# MCU.net
KiCad netlist of a schematic drawn in Altium Designer
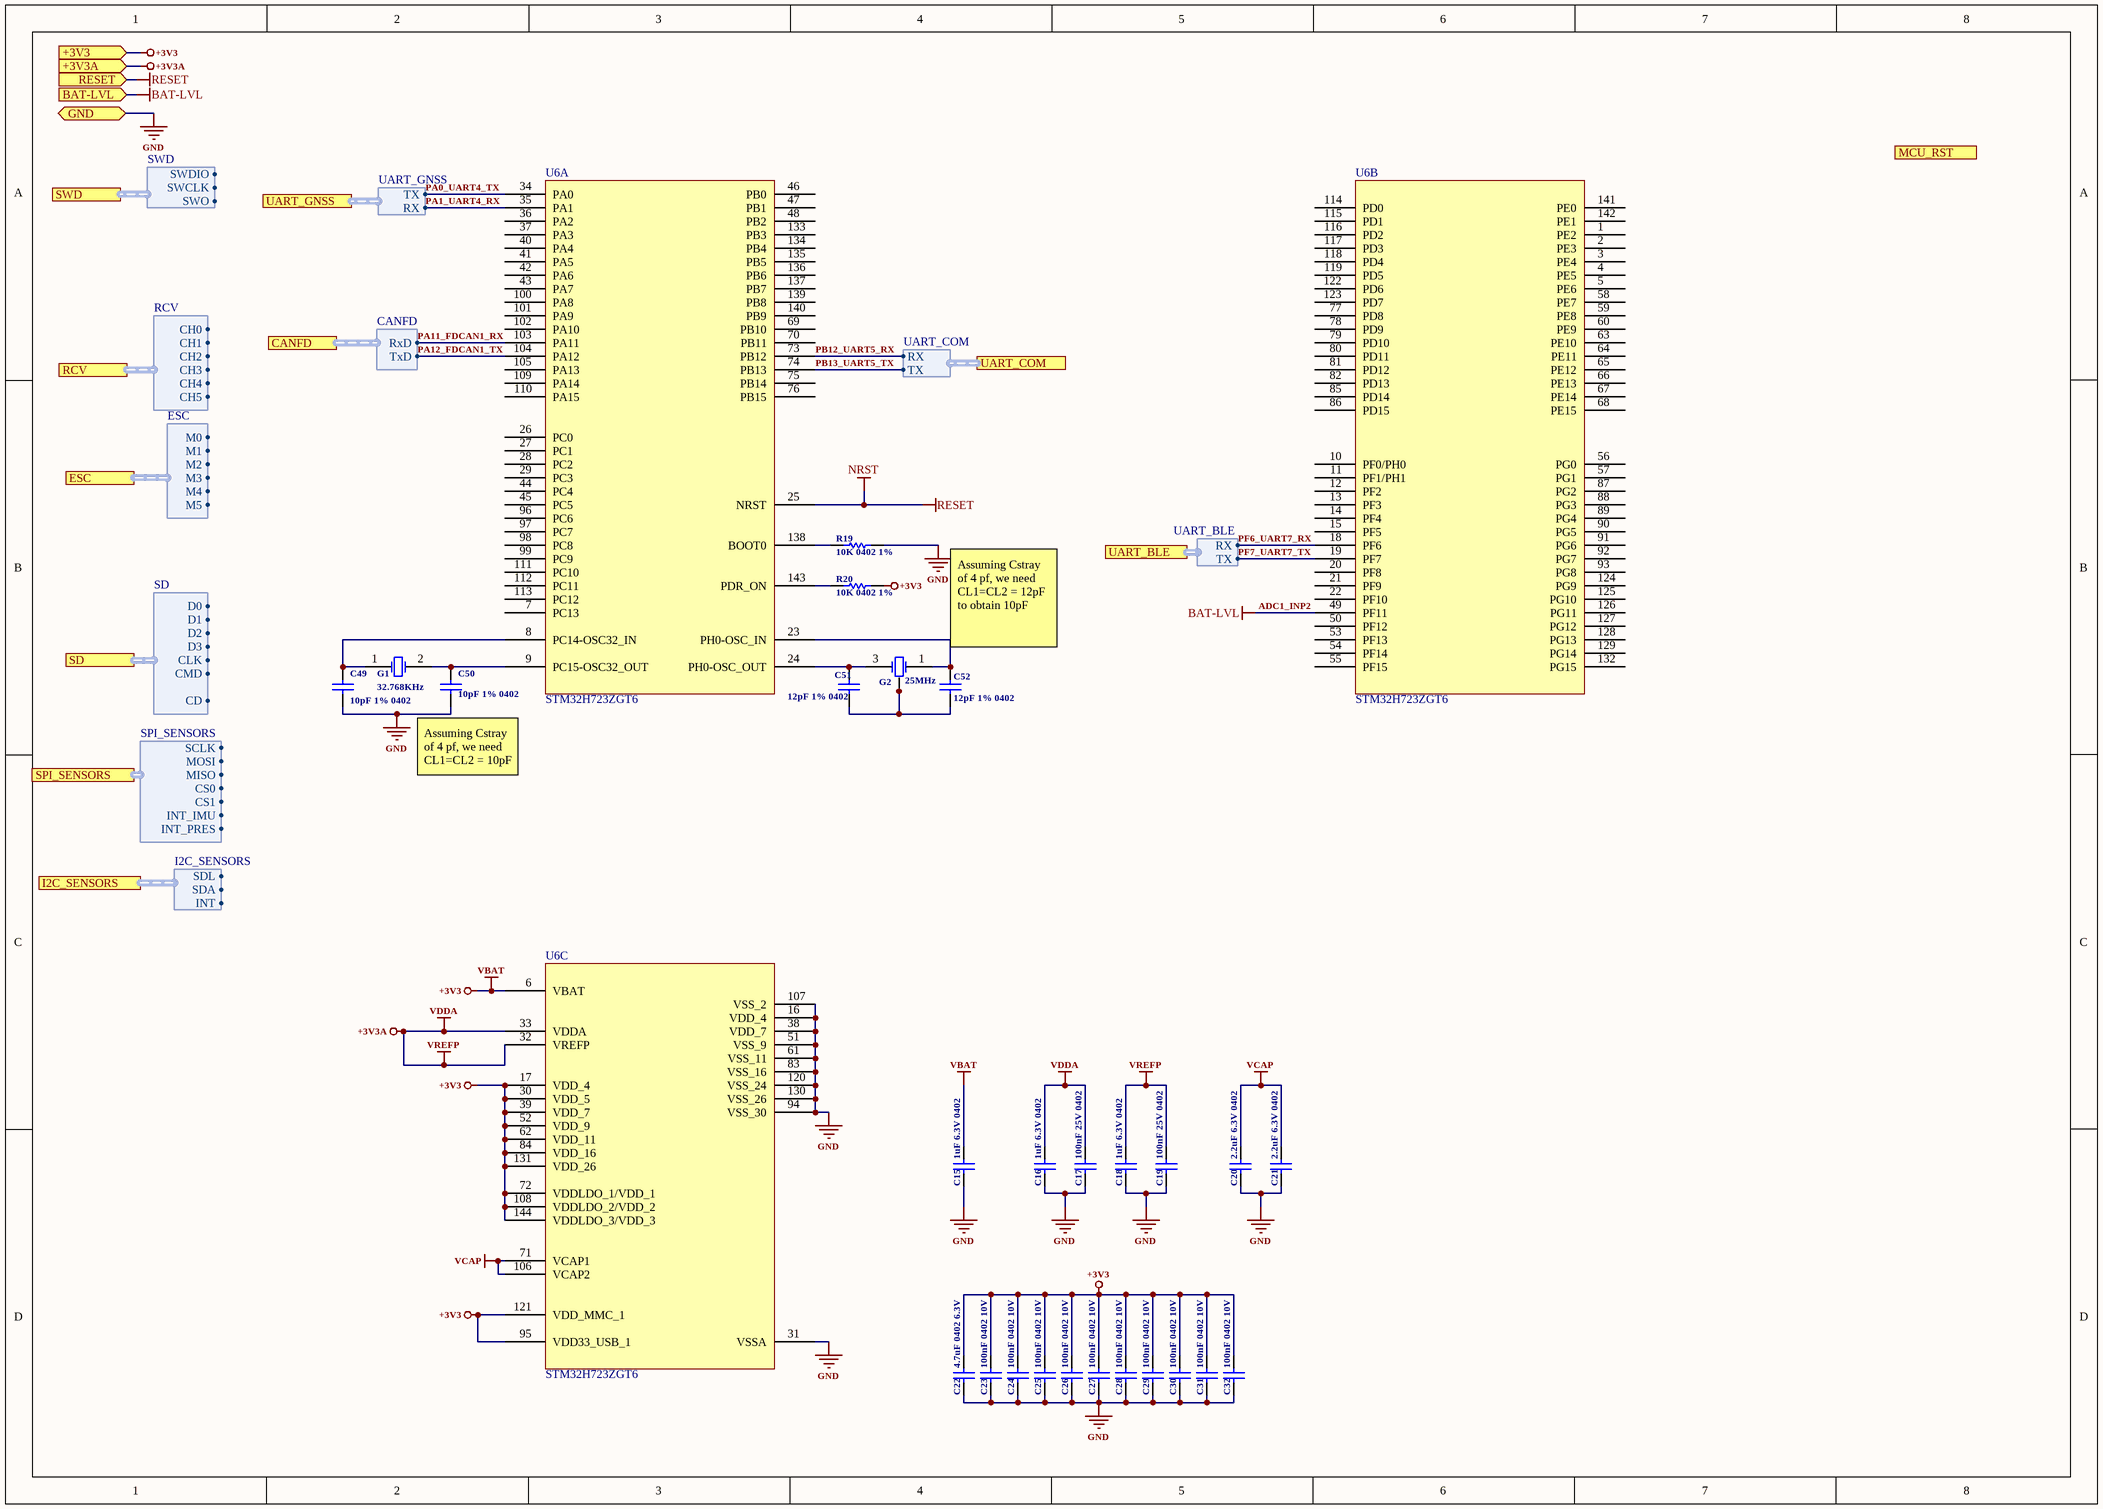
[diagram p0: MCU.SchDoc]

(export (version "E")
  (design (tool "Eeschema 10.0.6"))
  (components
    (comp (ref "C15")
      (value "1uF 6.3V 0402")
      (fields
        (field (name "MANUFACTURER") "Samsung")
        (field (name "MANUFACTURER PART NUMBER") "CL05A105KQ5NNNC")
      )
      (libsource (lib "CondensadoresGenericos") (part "CL05A105KQ5NNNC 1uF 0402"))
    )
    (comp (ref "C16")
      (value "1uF 6.3V 0402")
      (fields
        (field (name "MANUFACTURER") "Samsung")
        (field (name "MANUFACTURER PART NUMBER") "CL05A105KQ5NNNC")
      )
      (libsource (lib "CondensadoresGenericos") (part "CL05A105KQ5NNNC 1uF 0402"))
    )
    (comp (ref "C17")
      (value "100nF 25V 0402")
      (description "100nF, 25V, MLCC, 0402")
      (fields
        (field (name "MANUFACTURER") "Samsung")
        (field (name "MANUFACTURER PART NUMBER") "CL05A104KA5NNNC")
      )
      (libsource (lib "CondensadoresGenericos") (part "CL05A104KA5NNNC 100nf 0402"))
    )
    (comp (ref "C18")
      (value "1uF 6.3V 0402")
      (fields
        (field (name "MANUFACTURER") "Samsung")
        (field (name "MANUFACTURER PART NUMBER") "CL05A105KQ5NNNC")
      )
      (libsource (lib "CondensadoresGenericos") (part "CL05A105KQ5NNNC 1uF 0402"))
    )
    (comp (ref "C19")
      (value "100nF 25V 0402")
      (description "100nF, 25V, MLCC, 0402")
      (fields
        (field (name "MANUFACTURER") "Samsung")
        (field (name "MANUFACTURER PART NUMBER") "CL05A104KA5NNNC")
      )
      (libsource (lib "CondensadoresGenericos") (part "CL05A104KA5NNNC 100nf 0402"))
    )
    (comp (ref "C20")
      (value "2.2uF 6.3V 0402")
      (description "CAP CER 2.2UF 6.3V X5R 0402")
      (libsource (lib "CondensadoresGenericos") (part "CL05A225MQ5NNNC 2.2uF 0402"))
    )
    (comp (ref "C21")
      (value "2.2uF 6.3V 0402")
      (description "CAP CER 2.2UF 6.3V X5R 0402")
      (libsource (lib "CondensadoresGenericos") (part "CL05A225MQ5NNNC 2.2uF 0402"))
    )
    (comp (ref "C22")
      (value "4.7uF 0402 6.3V")
      (fields
        (field (name "MANUFACTURER") "Murata")
        (field (name "MANUFACTURER PART NUMBER") "GRM155R60J475ME87D")
        (field (name "VOLTAGE") "6.3 Vdc")
      )
      (libsource (lib "CondensadoresGenericos") (part "GRM155R60J475ME87D 4.7uF 0402 6.3V"))
    )
    (comp (ref "C23")
      (value "100nF 0402 10V")
      (description "Cap Ceramic 0.1uF 10V X5R 10% SMD 0402 85C Paper T/R")
      (fields
        (field (name "MANUFACTURER") "Samsung")
        (field (name "MANUFACTURER PART NUMBER") "CL05A104KP5NNNC")
      )
      (libsource (lib "CondensadoresGenericos") (part "CL05A104KP5NNNC 100nF 0402 10V"))
    )
    (comp (ref "C24")
      (value "100nF 0402 10V")
      (description "Cap Ceramic 0.1uF 10V X5R 10% SMD 0402 85C Paper T/R")
      (fields
        (field (name "MANUFACTURER") "Samsung")
        (field (name "MANUFACTURER PART NUMBER") "CL05A104KP5NNNC")
      )
      (libsource (lib "CondensadoresGenericos") (part "CL05A104KP5NNNC 100nF 0402 10V"))
    )
    (comp (ref "C25")
      (value "100nF 0402 10V")
      (description "Cap Ceramic 0.1uF 10V X5R 10% SMD 0402 85C Paper T/R")
      (fields
        (field (name "MANUFACTURER") "Samsung")
        (field (name "MANUFACTURER PART NUMBER") "CL05A104KP5NNNC")
      )
      (libsource (lib "CondensadoresGenericos") (part "CL05A104KP5NNNC 100nF 0402 10V"))
    )
    (comp (ref "C26")
      (value "100nF 0402 10V")
      (description "Cap Ceramic 0.1uF 10V X5R 10% SMD 0402 85C Paper T/R")
      (fields
        (field (name "MANUFACTURER") "Samsung")
        (field (name "MANUFACTURER PART NUMBER") "CL05A104KP5NNNC")
      )
      (libsource (lib "CondensadoresGenericos") (part "CL05A104KP5NNNC 100nF 0402 10V"))
    )
    (comp (ref "C27")
      (value "100nF 0402 10V")
      (description "Cap Ceramic 0.1uF 10V X5R 10% SMD 0402 85C Paper T/R")
      (fields
        (field (name "MANUFACTURER") "Samsung")
        (field (name "MANUFACTURER PART NUMBER") "CL05A104KP5NNNC")
      )
      (libsource (lib "CondensadoresGenericos") (part "CL05A104KP5NNNC 100nF 0402 10V"))
    )
    (comp (ref "C28")
      (value "100nF 0402 10V")
      (description "Cap Ceramic 0.1uF 10V X5R 10% SMD 0402 85C Paper T/R")
      (fields
        (field (name "MANUFACTURER") "Samsung")
        (field (name "MANUFACTURER PART NUMBER") "CL05A104KP5NNNC")
      )
      (libsource (lib "CondensadoresGenericos") (part "CL05A104KP5NNNC 100nF 0402 10V"))
    )
    (comp (ref "C29")
      (value "100nF 0402 10V")
      (description "Cap Ceramic 0.1uF 10V X5R 10% SMD 0402 85C Paper T/R")
      (fields
        (field (name "MANUFACTURER") "Samsung")
        (field (name "MANUFACTURER PART NUMBER") "CL05A104KP5NNNC")
      )
      (libsource (lib "CondensadoresGenericos") (part "CL05A104KP5NNNC 100nF 0402 10V"))
    )
    (comp (ref "C30")
      (value "100nF 0402 10V")
      (description "Cap Ceramic 0.1uF 10V X5R 10% SMD 0402 85C Paper T/R")
      (fields
        (field (name "MANUFACTURER") "Samsung")
        (field (name "MANUFACTURER PART NUMBER") "CL05A104KP5NNNC")
      )
      (libsource (lib "CondensadoresGenericos") (part "CL05A104KP5NNNC 100nF 0402 10V"))
    )
    (comp (ref "C31")
      (value "100nF 0402 10V")
      (description "Cap Ceramic 0.1uF 10V X5R 10% SMD 0402 85C Paper T/R")
      (fields
        (field (name "MANUFACTURER") "Samsung")
        (field (name "MANUFACTURER PART NUMBER") "CL05A104KP5NNNC")
      )
      (libsource (lib "CondensadoresGenericos") (part "CL05A104KP5NNNC 100nF 0402 10V"))
    )
    (comp (ref "C32")
      (value "100nF 0402 10V")
      (description "Cap Ceramic 0.1uF 10V X5R 10% SMD 0402 85C Paper T/R")
      (fields
        (field (name "MANUFACTURER") "Samsung")
        (field (name "MANUFACTURER PART NUMBER") "CL05A104KP5NNNC")
      )
      (libsource (lib "CondensadoresGenericos") (part "CL05A104KP5NNNC 100nF 0402 10V"))
    )
    (comp (ref "C49")
      (value "10pF 1% 0402")
      (description "10 pF ±1% 50V Ceramic Capacitor C0G, NP0 0402 (1005 Metric)")
      (libsource (lib "CondensadoresGenericos") (part "CC0402FRNPO9BN100"))
    )
    (comp (ref "C50")
      (value "10pF 1% 0402")
      (description "10 pF ±1% 50V Ceramic Capacitor C0G, NP0 0402 (1005 Metric)")
      (libsource (lib "CondensadoresGenericos") (part "CC0402FRNPO9BN100"))
    )
    (comp (ref "C51")
      (value "12pF 1% 0402")
      (description "12 pF ±1% 50V Ceramic Capacitor C0G, NP0 0402 (1005 Metric)")
      (libsource (lib "CondensadoresGenericos") (part "CC0402FRNPO9BN120"))
    )
    (comp (ref "C52")
      (value "12pF 1% 0402")
      (description "12 pF ±1% 50V Ceramic Capacitor C0G, NP0 0402 (1005 Metric)")
      (libsource (lib "CondensadoresGenericos") (part "CC0402FRNPO9BN120"))
    )
    (comp (ref "G1")
      (value "32.768KHz")
      (description "32.768 kHz ±10ppm Crystal 9pF 70 kOhms 2-SMD, No Lead")
      (libsource (lib "Cristals") (part "ECS-.327-9-34B-C-TR"))
    )
    (comp (ref "G2")
      (value "25MHz")
      (description "25 MHz ±10ppm Crystal 10pF 50 Ohms 4-SMD, No Lead")
      (libsource (lib "Cristals") (part "ECS-250-10-36B2-CTN-TR"))
    )
    (comp (ref "R19")
      (value "10K 0402 1%")
      (footprint "Resistor_0402")
      (description "RES SMD 10K OHM 1% 1/16W 0402")
      (fields
        (field (name "MANUFACTURER") "Yageo")
        (field (name "MANUFACTURER PART NUMBER") "AC0402FR-0710KL")
      )
      (libsource (lib "ResistenciasGenericas") (part "AC0402FR-0710KL 10K 0402 1%"))
    )
    (comp (ref "R20")
      (value "10K 0402 1%")
      (footprint "Resistor_0402")
      (description "RES SMD 10K OHM 1% 1/16W 0402")
      (fields
        (field (name "MANUFACTURER") "Yageo")
        (field (name "MANUFACTURER PART NUMBER") "AC0402FR-0710KL")
      )
      (libsource (lib "ResistenciasGenericas") (part "AC0402FR-0710KL 10K 0402 1%"))
    )
    (comp (ref "U6") (value "STM32H723ZGT6") (libsource (lib "STM_microcontrollers") (part "STM32H723ZGT6")))
  )
  (nets
    (net (code "11") (name "+3V3") (class "Default")
      (node (ref "C15") (pin "2") (pinfunction "2_2") (pintype "passive"))
      (node (ref "C22") (pin "2") (pinfunction "2_2") (pintype "passive"))
      (node (ref "C23") (pin "2") (pinfunction "2_2") (pintype "passive"))
      (node (ref "C24") (pin "2") (pinfunction "2_2") (pintype "passive"))
      (node (ref "C25") (pin "2") (pinfunction "2_2") (pintype "passive"))
      (node (ref "C26") (pin "2") (pinfunction "2_2") (pintype "passive"))
      (node (ref "C27") (pin "2") (pinfunction "2_2") (pintype "passive"))
      (node (ref "C28") (pin "2") (pinfunction "2_2") (pintype "passive"))
      (node (ref "C29") (pin "2") (pinfunction "2_2") (pintype "passive"))
      (node (ref "C30") (pin "2") (pinfunction "2_2") (pintype "passive"))
      (node (ref "C31") (pin "2") (pinfunction "2_2") (pintype "passive"))
      (node (ref "C32") (pin "2") (pinfunction "2_2") (pintype "passive"))
      (node (ref "R20") (pin "2") (pinfunction "2_2") (pintype "passive"))
      (node (ref "U6") (pin "108") (pinfunction "VDDLDO_2/VDD_2_108") (pintype "passive"))
      (node (ref "U6") (pin "121") (pinfunction "VDD_MMC_1_121") (pintype "passive"))
      (node (ref "U6") (pin "131") (pinfunction "VDD_26_131") (pintype "passive"))
      (node (ref "U6") (pin "144") (pinfunction "VDDLDO_3/VDD_3_144") (pintype "passive"))
      (node (ref "U6") (pin "17") (pinfunction "VDD_4_17") (pintype "passive"))
      (node (ref "U6") (pin "30") (pinfunction "VDD_5_30") (pintype "passive"))
      (node (ref "U6") (pin "39") (pinfunction "VDD_7_39") (pintype "passive"))
      (node (ref "U6") (pin "52") (pinfunction "VDD_9_52") (pintype "passive"))
      (node (ref "U6") (pin "6") (pinfunction "VBAT_6") (pintype "passive"))
      (node (ref "U6") (pin "62") (pinfunction "VDD_11_62") (pintype "passive"))
      (node (ref "U6") (pin "72") (pinfunction "VDDLDO_1/VDD_1_72") (pintype "passive"))
      (node (ref "U6") (pin "84") (pinfunction "VDD_16_84") (pintype "passive"))
      (node (ref "U6") (pin "95") (pinfunction "VDD33_USB_1_95") (pintype "passive"))
    )
    (net (code "12") (name "+3V3A") (class "Default")
      (node (ref "C16") (pin "2") (pinfunction "2_2") (pintype "passive"))
      (node (ref "C17") (pin "2") (pinfunction "2_2") (pintype "passive"))
      (node (ref "C18") (pin "2") (pinfunction "2_2") (pintype "passive"))
      (node (ref "C19") (pin "2") (pinfunction "2_2") (pintype "passive"))
      (node (ref "U6") (pin "32") (pinfunction "VREFP_32") (pintype "passive"))
      (node (ref "U6") (pin "33") (pinfunction "VDDA_33") (pintype "passive"))
    )
    (net (code "14") (name "/PA0_UART4_TX") (class "Default")
      (node (ref "U6") (pin "34") (pinfunction "PA0_34") (pintype "passive"))
    )
    (net (code "15") (name "/PA1_UART4_RX") (class "Default")
      (node (ref "U6") (pin "35") (pinfunction "PA1_35") (pintype "passive"))
    )
    (net (code "16") (name "/PA11_FDCAN1_RX") (class "Default")
      (node (ref "U6") (pin "103") (pinfunction "PA11_103") (pintype "passive"))
    )
    (net (code "17") (name "/PA12_FDCAN1_TX") (class "Default")
      (node (ref "U6") (pin "104") (pinfunction "PA12_104") (pintype "passive"))
    )
    (net (code "18") (name "/PB12_UART5_RX") (class "Default")
      (node (ref "U6") (pin "73") (pinfunction "PB12_73") (pintype "passive"))
    )
    (net (code "19") (name "/PB13_UART5_TX") (class "Default")
      (node (ref "U6") (pin "74") (pinfunction "PB13_74") (pintype "passive"))
    )
    (net (code "20") (name "/PF6_UART7_RX") (class "Default")
      (node (ref "U6") (pin "18") (pinfunction "PF6_18") (pintype "passive"))
    )
    (net (code "21") (name "/PF7_UART7_TX") (class "Default")
      (node (ref "U6") (pin "19") (pinfunction "PF7_19") (pintype "passive"))
    )
    (net (code "32") (name "BAT-LVL") (class "Default")
      (node (ref "U6") (pin "49") (pinfunction "PF11_49") (pintype "passive"))
    )
    (net (code "33") (name "GND") (class "Default")
      (node (ref "C15") (pin "1") (pinfunction "1_1") (pintype "passive"))
      (node (ref "C16") (pin "1") (pinfunction "1_1") (pintype "passive"))
      (node (ref "C17") (pin "1") (pinfunction "1_1") (pintype "passive"))
      (node (ref "C18") (pin "1") (pinfunction "1_1") (pintype "passive"))
      (node (ref "C19") (pin "1") (pinfunction "1_1") (pintype "passive"))
      (node (ref "C20") (pin "1") (pinfunction "1_1") (pintype "passive"))
      (node (ref "C21") (pin "1") (pinfunction "1_1") (pintype "passive"))
      (node (ref "C22") (pin "1") (pinfunction "1_1") (pintype "passive"))
      (node (ref "C23") (pin "1") (pinfunction "1_1") (pintype "passive"))
      (node (ref "C24") (pin "1") (pinfunction "1_1") (pintype "passive"))
      (node (ref "C25") (pin "1") (pinfunction "1_1") (pintype "passive"))
      (node (ref "C26") (pin "1") (pinfunction "1_1") (pintype "passive"))
      (node (ref "C27") (pin "1") (pinfunction "1_1") (pintype "passive"))
      (node (ref "C28") (pin "1") (pinfunction "1_1") (pintype "passive"))
      (node (ref "C29") (pin "1") (pinfunction "1_1") (pintype "passive"))
      (node (ref "C30") (pin "1") (pinfunction "1_1") (pintype "passive"))
      (node (ref "C31") (pin "1") (pinfunction "1_1") (pintype "passive"))
      (node (ref "C32") (pin "1") (pinfunction "1_1") (pintype "passive"))
      (node (ref "C49") (pin "1") (pinfunction "1_1") (pintype "passive"))
      (node (ref "C50") (pin "1") (pinfunction "1_1") (pintype "passive"))
      (node (ref "R19") (pin "2") (pinfunction "2_2") (pintype "passive"))
      (node (ref "U6") (pin "107") (pinfunction "VSS_2_107") (pintype "passive"))
      (node (ref "U6") (pin "120") (pinfunction "VSS_24_120") (pintype "passive"))
      (node (ref "U6") (pin "130") (pinfunction "VSS_26_130") (pintype "passive"))
      (node (ref "U6") (pin "16") (pinfunction "VDD_4_16") (pintype "passive"))
      (node (ref "U6") (pin "31") (pinfunction "VSSA_31") (pintype "passive"))
      (node (ref "U6") (pin "38") (pinfunction "VDD_7_38") (pintype "passive"))
      (node (ref "U6") (pin "51") (pinfunction "VSS_9_51") (pintype "passive"))
      (node (ref "U6") (pin "61") (pinfunction "VSS_11_61") (pintype "passive"))
      (node (ref "U6") (pin "83") (pinfunction "VSS_16_83") (pintype "passive"))
      (node (ref "U6") (pin "94") (pinfunction "VSS_30_94") (pintype "passive"))
    )
    (net (code "34") (name "NRST") (class "Default")
      (node (ref "U6") (pin "25") (pinfunction "NRST_25") (pintype "passive"))
    )
    (net (code "35") (name "Net-(C51-Pad1)") (class "Default")
      (node (ref "C51") (pin "1") (pinfunction "1_1") (pintype "passive"))
      (node (ref "C52") (pin "1") (pinfunction "1_1") (pintype "passive"))
      (node (ref "G2") (pin "2") (pinfunction "GND_2") (pintype "passive"))
      (node (ref "G2") (pin "4") (pinfunction "GND_4") (pintype "passive"))
    )
    (net (code "36") (name "Net-(G1-OSC1)") (class "Default")
      (node (ref "C49") (pin "2") (pinfunction "2_2") (pintype "passive"))
      (node (ref "G1") (pin "1") (pinfunction "OSC1_1") (pintype "passive"))
      (node (ref "U6") (pin "8") (pinfunction "PC14-OSC32_IN_8") (pintype "passive"))
    )
    (net (code "37") (name "Net-(G1-OSC2)") (class "Default")
      (node (ref "C50") (pin "2") (pinfunction "2_2") (pintype "passive"))
      (node (ref "G1") (pin "2") (pinfunction "OSC2_2") (pintype "passive"))
      (node (ref "U6") (pin "9") (pinfunction "PC15-OSC32_OUT_9") (pintype "passive"))
    )
    (net (code "38") (name "Net-(G2-OSC1)") (class "Default")
      (node (ref "C51") (pin "2") (pinfunction "2_2") (pintype "passive"))
      (node (ref "G2") (pin "3") (pinfunction "OSC1_3") (pintype "passive"))
      (node (ref "U6") (pin "24") (pinfunction "PH0-OSC_OUT_24") (pintype "passive"))
    )
    (net (code "39") (name "Net-(G2-OSC2)") (class "Default")
      (node (ref "C52") (pin "2") (pinfunction "2_2") (pintype "passive"))
      (node (ref "G2") (pin "1") (pinfunction "OSC2_1") (pintype "passive"))
      (node (ref "U6") (pin "23") (pinfunction "PH0-OSC_IN_23") (pintype "passive"))
    )
    (net (code "40") (name "Net-(U6A-BOOT0)") (class "Default")
      (node (ref "R19") (pin "1") (pinfunction "1_1") (pintype "passive"))
      (node (ref "U6") (pin "138") (pinfunction "BOOT0_138") (pintype "passive"))
    )
    (net (code "41") (name "Net-(U6A-PDR_ON)") (class "Default")
      (node (ref "R20") (pin "1") (pinfunction "1_1") (pintype "passive"))
      (node (ref "U6") (pin "143") (pinfunction "PDR_ON_143") (pintype "passive"))
    )
    (net (code "42") (name "VCAP") (class "Default")
      (node (ref "C20") (pin "2") (pinfunction "2_2") (pintype "passive"))
      (node (ref "C21") (pin "2") (pinfunction "2_2") (pintype "passive"))
      (node (ref "U6") (pin "106") (pinfunction "VCAP2_106") (pintype "passive"))
      (node (ref "U6") (pin "71") (pinfunction "VCAP1_71") (pintype "passive"))
    )
    (net (code "43") (name "unconnected-(U6A-PA2-Pad36)") (class "Default")
      (node (ref "U6") (pin "36") (pinfunction "PA2_36") (pintype "passive"))
    )
    (net (code "44") (name "unconnected-(U6A-PA3-Pad37)") (class "Default")
      (node (ref "U6") (pin "37") (pinfunction "PA3_37") (pintype "passive"))
    )
    (net (code "45") (name "unconnected-(U6A-PA4-Pad40)") (class "Default")
      (node (ref "U6") (pin "40") (pinfunction "PA4_40") (pintype "passive"))
    )
    (net (code "46") (name "unconnected-(U6A-PA5-Pad41)") (class "Default")
      (node (ref "U6") (pin "41") (pinfunction "PA5_41") (pintype "passive"))
    )
    (net (code "47") (name "unconnected-(U6A-PA6-Pad42)") (class "Default")
      (node (ref "U6") (pin "42") (pinfunction "PA6_42") (pintype "passive"))
    )
    (net (code "48") (name "unconnected-(U6A-PA7-Pad43)") (class "Default")
      (node (ref "U6") (pin "43") (pinfunction "PA7_43") (pintype "passive"))
    )
    (net (code "49") (name "unconnected-(U6A-PA8-Pad100)") (class "Default")
      (node (ref "U6") (pin "100") (pinfunction "PA8_100") (pintype "passive"))
    )
    (net (code "50") (name "unconnected-(U6A-PA9-Pad101)") (class "Default")
      (node (ref "U6") (pin "101") (pinfunction "PA9_101") (pintype "passive"))
    )
    (net (code "51") (name "unconnected-(U6A-PA10-Pad102)") (class "Default")
      (node (ref "U6") (pin "102") (pinfunction "PA10_102") (pintype "passive"))
    )
    (net (code "52") (name "unconnected-(U6A-PA13-Pad105)") (class "Default")
      (node (ref "U6") (pin "105") (pinfunction "PA13_105") (pintype "passive"))
    )
    (net (code "53") (name "unconnected-(U6A-PA14-Pad109)") (class "Default")
      (node (ref "U6") (pin "109") (pinfunction "PA14_109") (pintype "passive"))
    )
    (net (code "54") (name "unconnected-(U6A-PA15-Pad110)") (class "Default")
      (node (ref "U6") (pin "110") (pinfunction "PA15_110") (pintype "passive"))
    )
    (net (code "55") (name "unconnected-(U6A-PB0-Pad46)") (class "Default")
      (node (ref "U6") (pin "46") (pinfunction "PB0_46") (pintype "passive"))
    )
    (net (code "56") (name "unconnected-(U6A-PB1-Pad47)") (class "Default")
      (node (ref "U6") (pin "47") (pinfunction "PB1_47") (pintype "passive"))
    )
    (net (code "57") (name "unconnected-(U6A-PB2-Pad48)") (class "Default")
      (node (ref "U6") (pin "48") (pinfunction "PB2_48") (pintype "passive"))
    )
    (net (code "58") (name "unconnected-(U6A-PB3-Pad133)") (class "Default")
      (node (ref "U6") (pin "133") (pinfunction "PB3_133") (pintype "passive"))
    )
    (net (code "59") (name "unconnected-(U6A-PB4-Pad134)") (class "Default")
      (node (ref "U6") (pin "134") (pinfunction "PB4_134") (pintype "passive"))
    )
    (net (code "60") (name "unconnected-(U6A-PB5-Pad135)") (class "Default")
      (node (ref "U6") (pin "135") (pinfunction "PB5_135") (pintype "passive"))
    )
    (net (code "61") (name "unconnected-(U6A-PB6-Pad136)") (class "Default")
      (node (ref "U6") (pin "136") (pinfunction "PB6_136") (pintype "passive"))
    )
    (net (code "62") (name "unconnected-(U6A-PB7-Pad137)") (class "Default")
      (node (ref "U6") (pin "137") (pinfunction "PB7_137") (pintype "passive"))
    )
    (net (code "63") (name "unconnected-(U6A-PB8-Pad139)") (class "Default")
      (node (ref "U6") (pin "139") (pinfunction "PB8_139") (pintype "passive"))
    )
    (net (code "64") (name "unconnected-(U6A-PB9-Pad140)") (class "Default")
      (node (ref "U6") (pin "140") (pinfunction "PB9_140") (pintype "passive"))
    )
    (net (code "65") (name "unconnected-(U6A-PB10-Pad69)") (class "Default")
      (node (ref "U6") (pin "69") (pinfunction "PB10_69") (pintype "passive"))
    )
    (net (code "66") (name "unconnected-(U6A-PB11-Pad70)") (class "Default")
      (node (ref "U6") (pin "70") (pinfunction "PB11_70") (pintype "passive"))
    )
    (net (code "67") (name "unconnected-(U6A-PB14-Pad75)") (class "Default")
      (node (ref "U6") (pin "75") (pinfunction "PB14_75") (pintype "passive"))
    )
    (net (code "68") (name "unconnected-(U6A-PB15-Pad76)") (class "Default")
      (node (ref "U6") (pin "76") (pinfunction "PB15_76") (pintype "passive"))
    )
    (net (code "69") (name "unconnected-(U6A-PC0-Pad26)") (class "Default")
      (node (ref "U6") (pin "26") (pinfunction "PC0_26") (pintype "passive"))
    )
    (net (code "70") (name "unconnected-(U6A-PC1-Pad27)") (class "Default")
      (node (ref "U6") (pin "27") (pinfunction "PC1_27") (pintype "passive"))
    )
    (net (code "71") (name "unconnected-(U6A-PC2-Pad28)") (class "Default")
      (node (ref "U6") (pin "28") (pinfunction "PC2_28") (pintype "passive"))
    )
    (net (code "72") (name "unconnected-(U6A-PC3-Pad29)") (class "Default")
      (node (ref "U6") (pin "29") (pinfunction "PC3_29") (pintype "passive"))
    )
    (net (code "73") (name "unconnected-(U6A-PC4-Pad44)") (class "Default")
      (node (ref "U6") (pin "44") (pinfunction "PC4_44") (pintype "passive"))
    )
    (net (code "74") (name "unconnected-(U6A-PC5-Pad45)") (class "Default")
      (node (ref "U6") (pin "45") (pinfunction "PC5_45") (pintype "passive"))
    )
    (net (code "75") (name "unconnected-(U6A-PC6-Pad96)") (class "Default")
      (node (ref "U6") (pin "96") (pinfunction "PC6_96") (pintype "passive"))
    )
    (net (code "76") (name "unconnected-(U6A-PC7-Pad97)") (class "Default")
      (node (ref "U6") (pin "97") (pinfunction "PC7_97") (pintype "passive"))
    )
    (net (code "77") (name "unconnected-(U6A-PC8-Pad98)") (class "Default")
      (node (ref "U6") (pin "98") (pinfunction "PC8_98") (pintype "passive"))
    )
    (net (code "78") (name "unconnected-(U6A-PC9-Pad99)") (class "Default")
      (node (ref "U6") (pin "99") (pinfunction "PC9_99") (pintype "passive"))
    )
    (net (code "79") (name "unconnected-(U6A-PC10-Pad111)") (class "Default")
      (node (ref "U6") (pin "111") (pinfunction "PC10_111") (pintype "passive"))
    )
    (net (code "80") (name "unconnected-(U6A-PC11-Pad112)") (class "Default")
      (node (ref "U6") (pin "112") (pinfunction "PC11_112") (pintype "passive"))
    )
    (net (code "81") (name "unconnected-(U6A-PC12-Pad113)") (class "Default")
      (node (ref "U6") (pin "113") (pinfunction "PC12_113") (pintype "passive"))
    )
    (net (code "82") (name "unconnected-(U6A-PC13-Pad7)") (class "Default")
      (node (ref "U6") (pin "7") (pinfunction "PC13_7") (pintype "passive"))
    )
    (net (code "83") (name "unconnected-(U6B-PD0-Pad114)") (class "Default")
      (node (ref "U6") (pin "114") (pinfunction "PD0_114") (pintype "passive"))
    )
    (net (code "84") (name "unconnected-(U6B-PD1-Pad115)") (class "Default")
      (node (ref "U6") (pin "115") (pinfunction "PD1_115") (pintype "passive"))
    )
    (net (code "85") (name "unconnected-(U6B-PD2-Pad116)") (class "Default")
      (node (ref "U6") (pin "116") (pinfunction "PD2_116") (pintype "passive"))
    )
    (net (code "86") (name "unconnected-(U6B-PD3-Pad117)") (class "Default")
      (node (ref "U6") (pin "117") (pinfunction "PD3_117") (pintype "passive"))
    )
    (net (code "87") (name "unconnected-(U6B-PD4-Pad118)") (class "Default")
      (node (ref "U6") (pin "118") (pinfunction "PD4_118") (pintype "passive"))
    )
    (net (code "88") (name "unconnected-(U6B-PD5-Pad119)") (class "Default")
      (node (ref "U6") (pin "119") (pinfunction "PD5_119") (pintype "passive"))
    )
    (net (code "89") (name "unconnected-(U6B-PD6-Pad122)") (class "Default")
      (node (ref "U6") (pin "122") (pinfunction "PD6_122") (pintype "passive"))
    )
    (net (code "90") (name "unconnected-(U6B-PD7-Pad123)") (class "Default")
      (node (ref "U6") (pin "123") (pinfunction "PD7_123") (pintype "passive"))
    )
    (net (code "91") (name "unconnected-(U6B-PD8-Pad77)") (class "Default")
      (node (ref "U6") (pin "77") (pinfunction "PD8_77") (pintype "passive"))
    )
    (net (code "92") (name "unconnected-(U6B-PD9-Pad78)") (class "Default")
      (node (ref "U6") (pin "78") (pinfunction "PD9_78") (pintype "passive"))
    )
    (net (code "93") (name "unconnected-(U6B-PD10-Pad79)") (class "Default")
      (node (ref "U6") (pin "79") (pinfunction "PD10_79") (pintype "passive"))
    )
    (net (code "94") (name "unconnected-(U6B-PD11-Pad80)") (class "Default")
      (node (ref "U6") (pin "80") (pinfunction "PD11_80") (pintype "passive"))
    )
    (net (code "95") (name "unconnected-(U6B-PD12-Pad81)") (class "Default")
      (node (ref "U6") (pin "81") (pinfunction "PD12_81") (pintype "passive"))
    )
    (net (code "96") (name "unconnected-(U6B-PD13-Pad82)") (class "Default")
      (node (ref "U6") (pin "82") (pinfunction "PD13_82") (pintype "passive"))
    )
    (net (code "97") (name "unconnected-(U6B-PD14-Pad85)") (class "Default")
      (node (ref "U6") (pin "85") (pinfunction "PD14_85") (pintype "passive"))
    )
    (net (code "98") (name "unconnected-(U6B-PD15-Pad86)") (class "Default")
      (node (ref "U6") (pin "86") (pinfunction "PD15_86") (pintype "passive"))
    )
    (net (code "99") (name "unconnected-(U6B-PE0-Pad141)") (class "Default")
      (node (ref "U6") (pin "141") (pinfunction "PE0_141") (pintype "passive"))
    )
    (net (code "100") (name "unconnected-(U6B-PE1-Pad142)") (class "Default")
      (node (ref "U6") (pin "142") (pinfunction "PE1_142") (pintype "passive"))
    )
    (net (code "101") (name "unconnected-(U6B-PE2-Pad1)") (class "Default")
      (node (ref "U6") (pin "1") (pinfunction "PE2_1") (pintype "passive"))
    )
    (net (code "102") (name "unconnected-(U6B-PE3-Pad2)") (class "Default")
      (node (ref "U6") (pin "2") (pinfunction "PE3_2") (pintype "passive"))
    )
    (net (code "103") (name "unconnected-(U6B-PE4-Pad3)") (class "Default")
      (node (ref "U6") (pin "3") (pinfunction "PE4_3") (pintype "passive"))
    )
    (net (code "104") (name "unconnected-(U6B-PE5-Pad4)") (class "Default")
      (node (ref "U6") (pin "4") (pinfunction "PE5_4") (pintype "passive"))
    )
    (net (code "105") (name "unconnected-(U6B-PE6-Pad5)") (class "Default")
      (node (ref "U6") (pin "5") (pinfunction "PE6_5") (pintype "passive"))
    )
    (net (code "106") (name "unconnected-(U6B-PE7-Pad58)") (class "Default")
      (node (ref "U6") (pin "58") (pinfunction "PE7_58") (pintype "passive"))
    )
    (net (code "107") (name "unconnected-(U6B-PE8-Pad59)") (class "Default")
      (node (ref "U6") (pin "59") (pinfunction "PE8_59") (pintype "passive"))
    )
    (net (code "108") (name "unconnected-(U6B-PE9-Pad60)") (class "Default")
      (node (ref "U6") (pin "60") (pinfunction "PE9_60") (pintype "passive"))
    )
    (net (code "109") (name "unconnected-(U6B-PE10-Pad63)") (class "Default")
      (node (ref "U6") (pin "63") (pinfunction "PE10_63") (pintype "passive"))
    )
    (net (code "110") (name "unconnected-(U6B-PE11-Pad64)") (class "Default")
      (node (ref "U6") (pin "64") (pinfunction "PE11_64") (pintype "passive"))
    )
    (net (code "111") (name "unconnected-(U6B-PE12-Pad65)") (class "Default")
      (node (ref "U6") (pin "65") (pinfunction "PE12_65") (pintype "passive"))
    )
    (net (code "112") (name "unconnected-(U6B-PE13-Pad66)") (class "Default")
      (node (ref "U6") (pin "66") (pinfunction "PE13_66") (pintype "passive"))
    )
    (net (code "113") (name "unconnected-(U6B-PE14-Pad67)") (class "Default")
      (node (ref "U6") (pin "67") (pinfunction "PE14_67") (pintype "passive"))
    )
    (net (code "114") (name "unconnected-(U6B-PE15-Pad68)") (class "Default")
      (node (ref "U6") (pin "68") (pinfunction "PE15_68") (pintype "passive"))
    )
    (net (code "115") (name "unconnected-(U6B-PF0{slash}PH0-Pad10)") (class "Default")
      (node (ref "U6") (pin "10") (pinfunction "PF0/PH0_10") (pintype "passive"))
    )
    (net (code "116") (name "unconnected-(U6B-PF1{slash}PH1-Pad11)") (class "Default")
      (node (ref "U6") (pin "11") (pinfunction "PF1/PH1_11") (pintype "passive"))
    )
    (net (code "117") (name "unconnected-(U6B-PF2-Pad12)") (class "Default")
      (node (ref "U6") (pin "12") (pinfunction "PF2_12") (pintype "passive"))
    )
    (net (code "118") (name "unconnected-(U6B-PF3-Pad13)") (class "Default")
      (node (ref "U6") (pin "13") (pinfunction "PF3_13") (pintype "passive"))
    )
    (net (code "119") (name "unconnected-(U6B-PF4-Pad14)") (class "Default")
      (node (ref "U6") (pin "14") (pinfunction "PF4_14") (pintype "passive"))
    )
    (net (code "120") (name "unconnected-(U6B-PF5-Pad15)") (class "Default")
      (node (ref "U6") (pin "15") (pinfunction "PF5_15") (pintype "passive"))
    )
    (net (code "121") (name "unconnected-(U6B-PF8-Pad20)") (class "Default")
      (node (ref "U6") (pin "20") (pinfunction "PF8_20") (pintype "passive"))
    )
    (net (code "122") (name "unconnected-(U6B-PF9-Pad21)") (class "Default")
      (node (ref "U6") (pin "21") (pinfunction "PF9_21") (pintype "passive"))
    )
    (net (code "123") (name "unconnected-(U6B-PF10-Pad22)") (class "Default")
      (node (ref "U6") (pin "22") (pinfunction "PF10_22") (pintype "passive"))
    )
    (net (code "124") (name "unconnected-(U6B-PF12-Pad50)") (class "Default")
      (node (ref "U6") (pin "50") (pinfunction "PF12_50") (pintype "passive"))
    )
    (net (code "125") (name "unconnected-(U6B-PF13-Pad53)") (class "Default")
      (node (ref "U6") (pin "53") (pinfunction "PF13_53") (pintype "passive"))
    )
    (net (code "126") (name "unconnected-(U6B-PF14-Pad54)") (class "Default")
      (node (ref "U6") (pin "54") (pinfunction "PF14_54") (pintype "passive"))
    )
    (net (code "127") (name "unconnected-(U6B-PF15-Pad55)") (class "Default")
      (node (ref "U6") (pin "55") (pinfunction "PF15_55") (pintype "passive"))
    )
    (net (code "128") (name "unconnected-(U6B-PG0-Pad56)") (class "Default")
      (node (ref "U6") (pin "56") (pinfunction "PG0_56") (pintype "passive"))
    )
    (net (code "129") (name "unconnected-(U6B-PG1-Pad57)") (class "Default")
      (node (ref "U6") (pin "57") (pinfunction "PG1_57") (pintype "passive"))
    )
    (net (code "130") (name "unconnected-(U6B-PG2-Pad87)") (class "Default")
      (node (ref "U6") (pin "87") (pinfunction "PG2_87") (pintype "passive"))
    )
    (net (code "131") (name "unconnected-(U6B-PG3-Pad88)") (class "Default")
      (node (ref "U6") (pin "88") (pinfunction "PG3_88") (pintype "passive"))
    )
    (net (code "132") (name "unconnected-(U6B-PG4-Pad89)") (class "Default")
      (node (ref "U6") (pin "89") (pinfunction "PG4_89") (pintype "passive"))
    )
    (net (code "133") (name "unconnected-(U6B-PG5-Pad90)") (class "Default")
      (node (ref "U6") (pin "90") (pinfunction "PG5_90") (pintype "passive"))
    )
    (net (code "134") (name "unconnected-(U6B-PG6-Pad91)") (class "Default")
      (node (ref "U6") (pin "91") (pinfunction "PG6_91") (pintype "passive"))
    )
    (net (code "135") (name "unconnected-(U6B-PG7-Pad92)") (class "Default")
      (node (ref "U6") (pin "92") (pinfunction "PG7_92") (pintype "passive"))
    )
    (net (code "136") (name "unconnected-(U6B-PG8-Pad93)") (class "Default")
      (node (ref "U6") (pin "93") (pinfunction "PG8_93") (pintype "passive"))
    )
    (net (code "137") (name "unconnected-(U6B-PG9-Pad124)") (class "Default")
      (node (ref "U6") (pin "124") (pinfunction "PG9_124") (pintype "passive"))
    )
    (net (code "138") (name "unconnected-(U6B-PG10-Pad125)") (class "Default")
      (node (ref "U6") (pin "125") (pinfunction "PG10_125") (pintype "passive"))
    )
    (net (code "139") (name "unconnected-(U6B-PG11-Pad126)") (class "Default")
      (node (ref "U6") (pin "126") (pinfunction "PG11_126") (pintype "passive"))
    )
    (net (code "140") (name "unconnected-(U6B-PG12-Pad127)") (class "Default")
      (node (ref "U6") (pin "127") (pinfunction "PG12_127") (pintype "passive"))
    )
    (net (code "141") (name "unconnected-(U6B-PG13-Pad128)") (class "Default")
      (node (ref "U6") (pin "128") (pinfunction "PG13_128") (pintype "passive"))
    )
    (net (code "142") (name "unconnected-(U6B-PG14-Pad129)") (class "Default")
      (node (ref "U6") (pin "129") (pinfunction "PG14_129") (pintype "passive"))
    )
    (net (code "143") (name "unconnected-(U6B-PG15-Pad132)") (class "Default")
      (node (ref "U6") (pin "132") (pinfunction "PG15_132") (pintype "passive"))
    )
  )
)
